# High_Side_Switch.net
KiCad netlist of a schematic drawn in Altium Designer
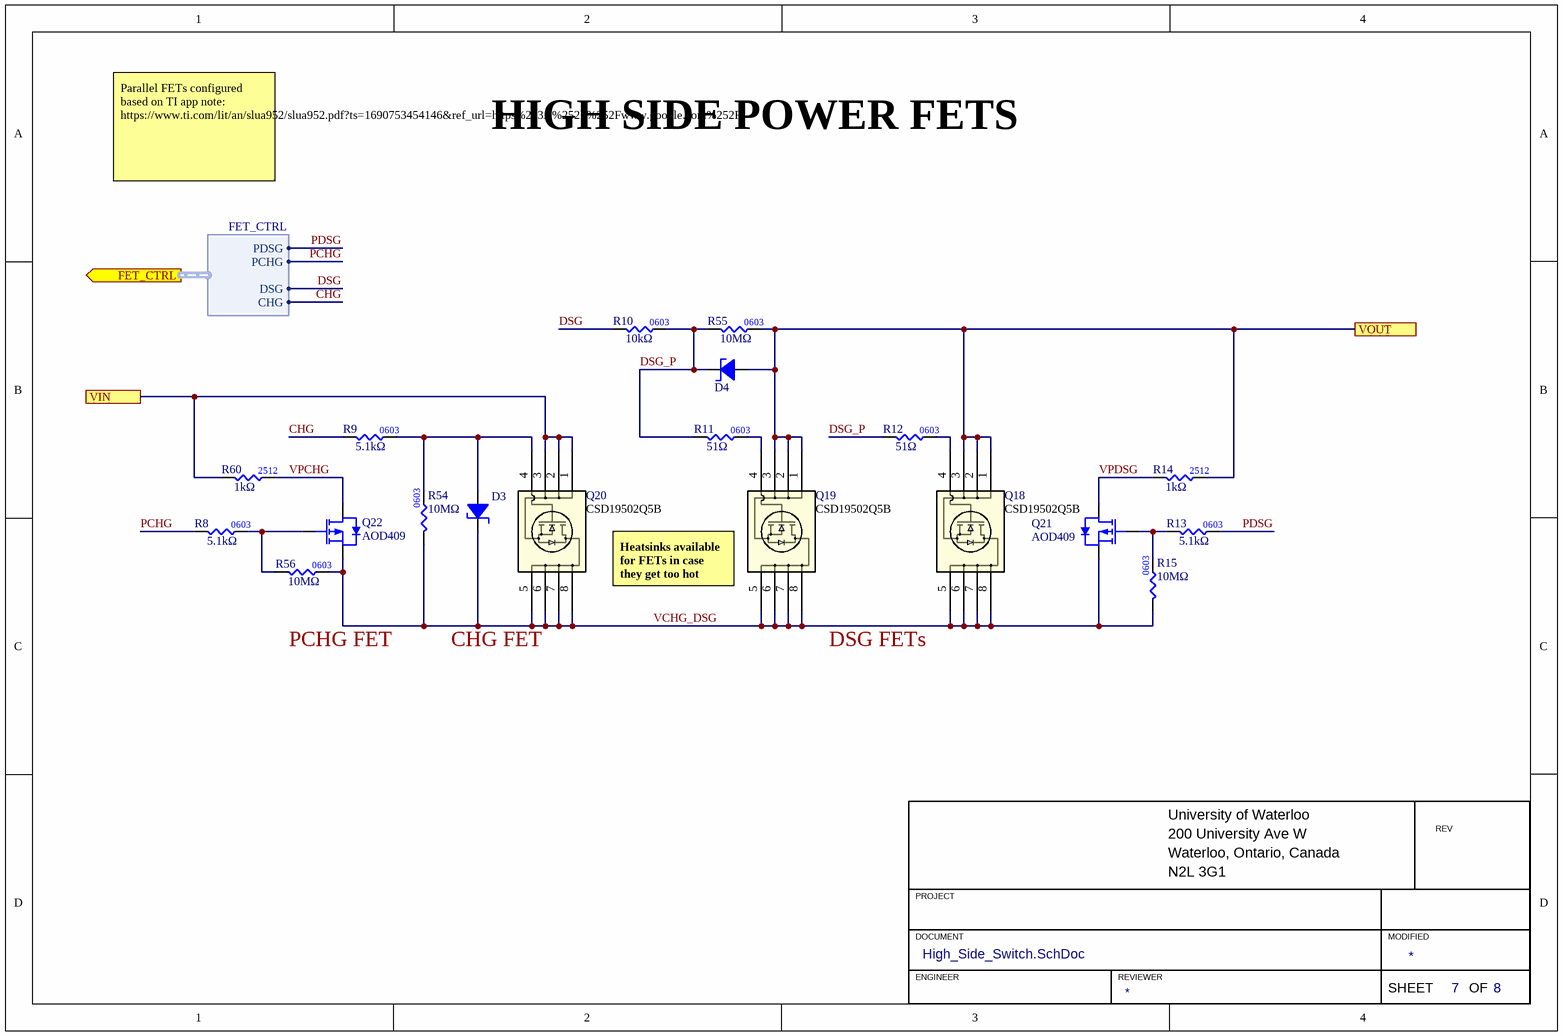
[diagram p0: High_Side_Switch.SchDoc]

(export (version "E")
  (design (tool "Eeschema 10.0.6"))
  (components
    (comp (ref "D3")
      (value "DIO_ZENER_16V")
      (footprint "SOD-123_FLAT")
      (description "DIODE ZENER 16V 500MW SOD123")
      (libsource (lib "Personal_Schematic_Library_2022") (part "DIO_ZENER_16V"))
    )
    (comp (ref "D4")
      (value "DIO_ZENER_16V")
      (footprint "SOD-123_FLAT")
      (description "DIODE ZENER 16V 500MW SOD123")
      (libsource (lib "Personal_Schematic_Library_2022") (part "DIO_ZENER_16V"))
    )
    (comp (ref "Q18")
      (value "CSD19502Q5B")
      (footprint "DFN5060")
      (description "MOSFET N-CH 80V 100A 8VSON")
      (fields (field (name "MANUFACTURER PART NUMBER 1") "CSD19502Q5B"))
      (libsource (lib "Personal_Schematic_Library_2022") (part "NMOS_CSD19502Q5B_80V_100A"))
    )
    (comp (ref "Q19")
      (value "CSD19502Q5B")
      (footprint "DFN5060")
      (description "MOSFET N-CH 80V 100A 8VSON")
      (fields (field (name "MANUFACTURER PART NUMBER 1") "CSD19502Q5B"))
      (libsource (lib "Personal_Schematic_Library_2022") (part "NMOS_CSD19502Q5B_80V_100A"))
    )
    (comp (ref "Q20")
      (value "CSD19502Q5B")
      (footprint "DFN5060")
      (description "MOSFET N-CH 80V 100A 8VSON")
      (fields (field (name "MANUFACTURER PART NUMBER 1") "CSD19502Q5B"))
      (libsource (lib "Personal_Schematic_Library_2022") (part "NMOS_CSD19502Q5B_80V_100A"))
    )
    (comp (ref "Q21")
      (value "PMOS_60V_26A")
      (footprint "TO-252 AOSMD")
      (description "MOSFET P-CH 60V 26A TO252")
      (fields (field (name "MANUFACTURER PART NUMBER 1") "AOD409"))
      (libsource (lib "Personal_Schematic_Library_2022") (part "PMOS_60V_26A"))
    )
    (comp (ref "Q22")
      (value "PMOS_60V_26A")
      (footprint "TO-252 AOSMD")
      (description "MOSFET P-CH 60V 26A TO252")
      (fields (field (name "MANUFACTURER PART NUMBER 1") "AOD409"))
      (libsource (lib "Personal_Schematic_Library_2022") (part "PMOS_60V_26A"))
    )
    (comp (ref "R8")
      (value "5.1kΩ")
      (footprint "RES0603")
      (description "RES 5.1K OHM 1% 1/10W 0603")
      (fields (field (name "Comment") "RES_5.1kΩ_0603_1%"))
      (libsource (lib "Personal_Schematic_Library_2022") (part "RES_5.1kΩ_0603_1%"))
    )
    (comp (ref "R9")
      (value "5.1kΩ")
      (footprint "RES0603")
      (description "RES 5.1K OHM 1% 1/10W 0603")
      (fields (field (name "Comment") "RES_5.1kΩ_0603_1%"))
      (libsource (lib "Personal_Schematic_Library_2022") (part "RES_5.1kΩ_0603_1%"))
    )
    (comp (ref "R10")
      (value "10kΩ")
      (footprint "RES0603")
      (description "RES 10K OHM 1% 1/8W 0603")
      (fields (field (name "Comment") "RES_10kΩ_0603_1%"))
      (libsource (lib "Personal_Schematic_Library_2022") (part "RES_10kΩ_0603_1%"))
    )
    (comp (ref "R11")
      (value "51Ω")
      (footprint "RES0603")
      (description "RES 51 OHM 1% 1/10W 0603")
      (fields (field (name "Comment") "RES_51Ω_0603_1%"))
      (libsource (lib "Personal_Schematic_Library_2022") (part "RES_51Ω_0603_1%"))
    )
    (comp (ref "R12")
      (value "51Ω")
      (footprint "RES0603")
      (description "RES 51 OHM 1% 1/10W 0603")
      (fields (field (name "Comment") "RES_51Ω_0603_1%"))
      (libsource (lib "Personal_Schematic_Library_2022") (part "RES_51Ω_0603_1%"))
    )
    (comp (ref "R13")
      (value "5.1kΩ")
      (footprint "RES0603")
      (description "RES 5.1K OHM 1% 1/10W 0603")
      (fields (field (name "Comment") "RES_5.1kΩ_0603_1%"))
      (libsource (lib "Personal_Schematic_Library_2022") (part "RES_5.1kΩ_0603_1%"))
    )
    (comp (ref "R14")
      (value "1kΩ")
      (footprint "RES2512")
      (description "RES SMD 1K OHM 1% 3W 2512")
      (fields (field (name "Comment") "RES_1kΩ_2512_1%"))
      (libsource (lib "Personal_Schematic_Library_2022") (part "RES_1kΩ_2512_1%"))
    )
    (comp (ref "R15")
      (value "10MΩ")
      (footprint "RES0603")
      (description "RES 10M OHM 1% 1/10W 0603")
      (fields (field (name "Comment") "RES_10MΩ_0603_1%"))
      (libsource (lib "Personal_Schematic_Library_2022") (part "RES_10MΩ_0603_1%"))
    )
    (comp (ref "R54")
      (value "10MΩ")
      (footprint "RES0603")
      (description "RES 10M OHM 1% 1/10W 0603")
      (fields (field (name "Comment") "RES_10MΩ_0603_1%"))
      (libsource (lib "Personal_Schematic_Library_2022") (part "RES_10MΩ_0603_1%"))
    )
    (comp (ref "R55")
      (value "10MΩ")
      (footprint "RES0603")
      (description "RES 10M OHM 1% 1/10W 0603")
      (fields (field (name "Comment") "RES_10MΩ_0603_1%"))
      (libsource (lib "Personal_Schematic_Library_2022") (part "RES_10MΩ_0603_1%"))
    )
    (comp (ref "R56")
      (value "10MΩ")
      (footprint "RES0603")
      (description "RES 10M OHM 1% 1/10W 0603")
      (fields (field (name "Comment") "RES_10MΩ_0603_1%"))
      (libsource (lib "Personal_Schematic_Library_2022") (part "RES_10MΩ_0603_1%"))
    )
    (comp (ref "R60")
      (value "1kΩ")
      (footprint "RES2512")
      (description "RES SMD 1K OHM 1% 3W 2512")
      (fields (field (name "Comment") "RES_1kΩ_2512_1%"))
      (libsource (lib "Personal_Schematic_Library_2022") (part "RES_1kΩ_2512_1%"))
    )
  )
  (nets
    (net (code "2") (name "/CHG") (class "Default")
      (node (ref "R9") (pin "1") (pinfunction "1_1") (pintype "passive"))
    )
    (net (code "3") (name "/DSG") (class "Default")
      (node (ref "R10") (pin "1") (pinfunction "1_1") (pintype "passive"))
    )
    (net (code "4") (name "/DSG_P") (class "Default")
      (node (ref "D4") (pin "2") (pinfunction "Cathode_2") (pintype "passive"))
      (node (ref "R10") (pin "2") (pinfunction "2_2") (pintype "passive"))
      (node (ref "R11") (pin "1") (pinfunction "1_1") (pintype "passive"))
      (node (ref "R12") (pin "1") (pinfunction "1_1") (pintype "passive"))
      (node (ref "R55") (pin "1") (pinfunction "1_1") (pintype "passive"))
    )
    (net (code "5") (name "/PCHG") (class "Default")
      (node (ref "R8") (pin "1") (pinfunction "1_1") (pintype "passive"))
    )
    (net (code "6") (name "/PDSG") (class "Default")
      (node (ref "R13") (pin "2") (pinfunction "2_2") (pintype "passive"))
    )
    (net (code "7") (name "/VCHG_DSG") (class "Default")
      (node (ref "D3") (pin "2") (pinfunction "Cathode_2") (pintype "passive"))
      (node (ref "Q18") (pin "5") (pinfunction "D_5") (pintype "passive"))
      (node (ref "Q18") (pin "6") (pinfunction "D_6") (pintype "passive"))
      (node (ref "Q18") (pin "7") (pinfunction "D_7") (pintype "passive"))
      (node (ref "Q18") (pin "8") (pinfunction "D_8") (pintype "passive"))
      (node (ref "Q19") (pin "5") (pinfunction "D_5") (pintype "passive"))
      (node (ref "Q19") (pin "6") (pinfunction "D_6") (pintype "passive"))
      (node (ref "Q19") (pin "7") (pinfunction "D_7") (pintype "passive"))
      (node (ref "Q19") (pin "8") (pinfunction "D_8") (pintype "passive"))
      (node (ref "Q20") (pin "5") (pinfunction "D_5") (pintype "passive"))
      (node (ref "Q20") (pin "6") (pinfunction "D_6") (pintype "passive"))
      (node (ref "Q20") (pin "7") (pinfunction "D_7") (pintype "passive"))
      (node (ref "Q20") (pin "8") (pinfunction "D_8") (pintype "passive"))
      (node (ref "Q21") (pin "3") (pinfunction "Source_3") (pintype "passive"))
      (node (ref "Q22") (pin "3") (pinfunction "Source_3") (pintype "passive"))
      (node (ref "R15") (pin "1") (pinfunction "1_1") (pintype "passive"))
      (node (ref "R54") (pin "1") (pinfunction "1_1") (pintype "passive"))
      (node (ref "R56") (pin "2") (pinfunction "2_2") (pintype "passive"))
    )
    (net (code "8") (name "/VIN") (class "Default")
      (node (ref "Q20") (pin "1") (pinfunction "S_1") (pintype "passive"))
      (node (ref "Q20") (pin "2") (pinfunction "S_2") (pintype "passive"))
      (node (ref "Q20") (pin "3") (pinfunction "S_3") (pintype "passive"))
      (node (ref "R60") (pin "1") (pinfunction "1_1") (pintype "passive"))
    )
    (net (code "9") (name "/VOUT") (class "Default")
      (node (ref "D4") (pin "1") (pinfunction "Anode_1") (pintype "passive"))
      (node (ref "Q18") (pin "1") (pinfunction "S_1") (pintype "passive"))
      (node (ref "Q18") (pin "2") (pinfunction "S_2") (pintype "passive"))
      (node (ref "Q18") (pin "3") (pinfunction "S_3") (pintype "passive"))
      (node (ref "Q19") (pin "1") (pinfunction "S_1") (pintype "passive"))
      (node (ref "Q19") (pin "2") (pinfunction "S_2") (pintype "passive"))
      (node (ref "Q19") (pin "3") (pinfunction "S_3") (pintype "passive"))
      (node (ref "R14") (pin "2") (pinfunction "2_2") (pintype "passive"))
      (node (ref "R55") (pin "2") (pinfunction "2_2") (pintype "passive"))
    )
    (net (code "10") (name "/VPCHG") (class "Default")
      (node (ref "Q22") (pin "2") (pinfunction "Drain_2") (pintype "passive"))
      (node (ref "R60") (pin "2") (pinfunction "2_2") (pintype "passive"))
    )
    (net (code "11") (name "/VPDSG") (class "Default")
      (node (ref "Q21") (pin "2") (pinfunction "Drain_2") (pintype "passive"))
      (node (ref "R14") (pin "1") (pinfunction "1_1") (pintype "passive"))
    )
    (net (code "13") (name "Net-(D3-Anode)") (class "Default")
      (node (ref "D3") (pin "1") (pinfunction "Anode_1") (pintype "passive"))
      (node (ref "Q20") (pin "4") (pinfunction "G_4") (pintype "passive"))
      (node (ref "R54") (pin "2") (pinfunction "2_2") (pintype "passive"))
      (node (ref "R9") (pin "2") (pinfunction "2_2") (pintype "passive"))
    )
    (net (code "14") (name "Net-(Q18-G)") (class "Default")
      (node (ref "Q18") (pin "4") (pinfunction "G_4") (pintype "passive"))
      (node (ref "R12") (pin "2") (pinfunction "2_2") (pintype "passive"))
    )
    (net (code "15") (name "Net-(Q19-G)") (class "Default")
      (node (ref "Q19") (pin "4") (pinfunction "G_4") (pintype "passive"))
      (node (ref "R11") (pin "2") (pinfunction "2_2") (pintype "passive"))
    )
    (net (code "16") (name "Net-(Q21-Gate)") (class "Default")
      (node (ref "Q21") (pin "1") (pinfunction "Gate_1") (pintype "passive"))
      (node (ref "R13") (pin "1") (pinfunction "1_1") (pintype "passive"))
      (node (ref "R15") (pin "2") (pinfunction "2_2") (pintype "passive"))
    )
    (net (code "17") (name "Net-(Q22-Gate)") (class "Default")
      (node (ref "Q22") (pin "1") (pinfunction "Gate_1") (pintype "passive"))
      (node (ref "R56") (pin "1") (pinfunction "1_1") (pintype "passive"))
      (node (ref "R8") (pin "2") (pinfunction "2_2") (pintype "passive"))
    )
  )
)
